# isolated_USB.net
KiCad netlist of a schematic drawn in Altium Designer
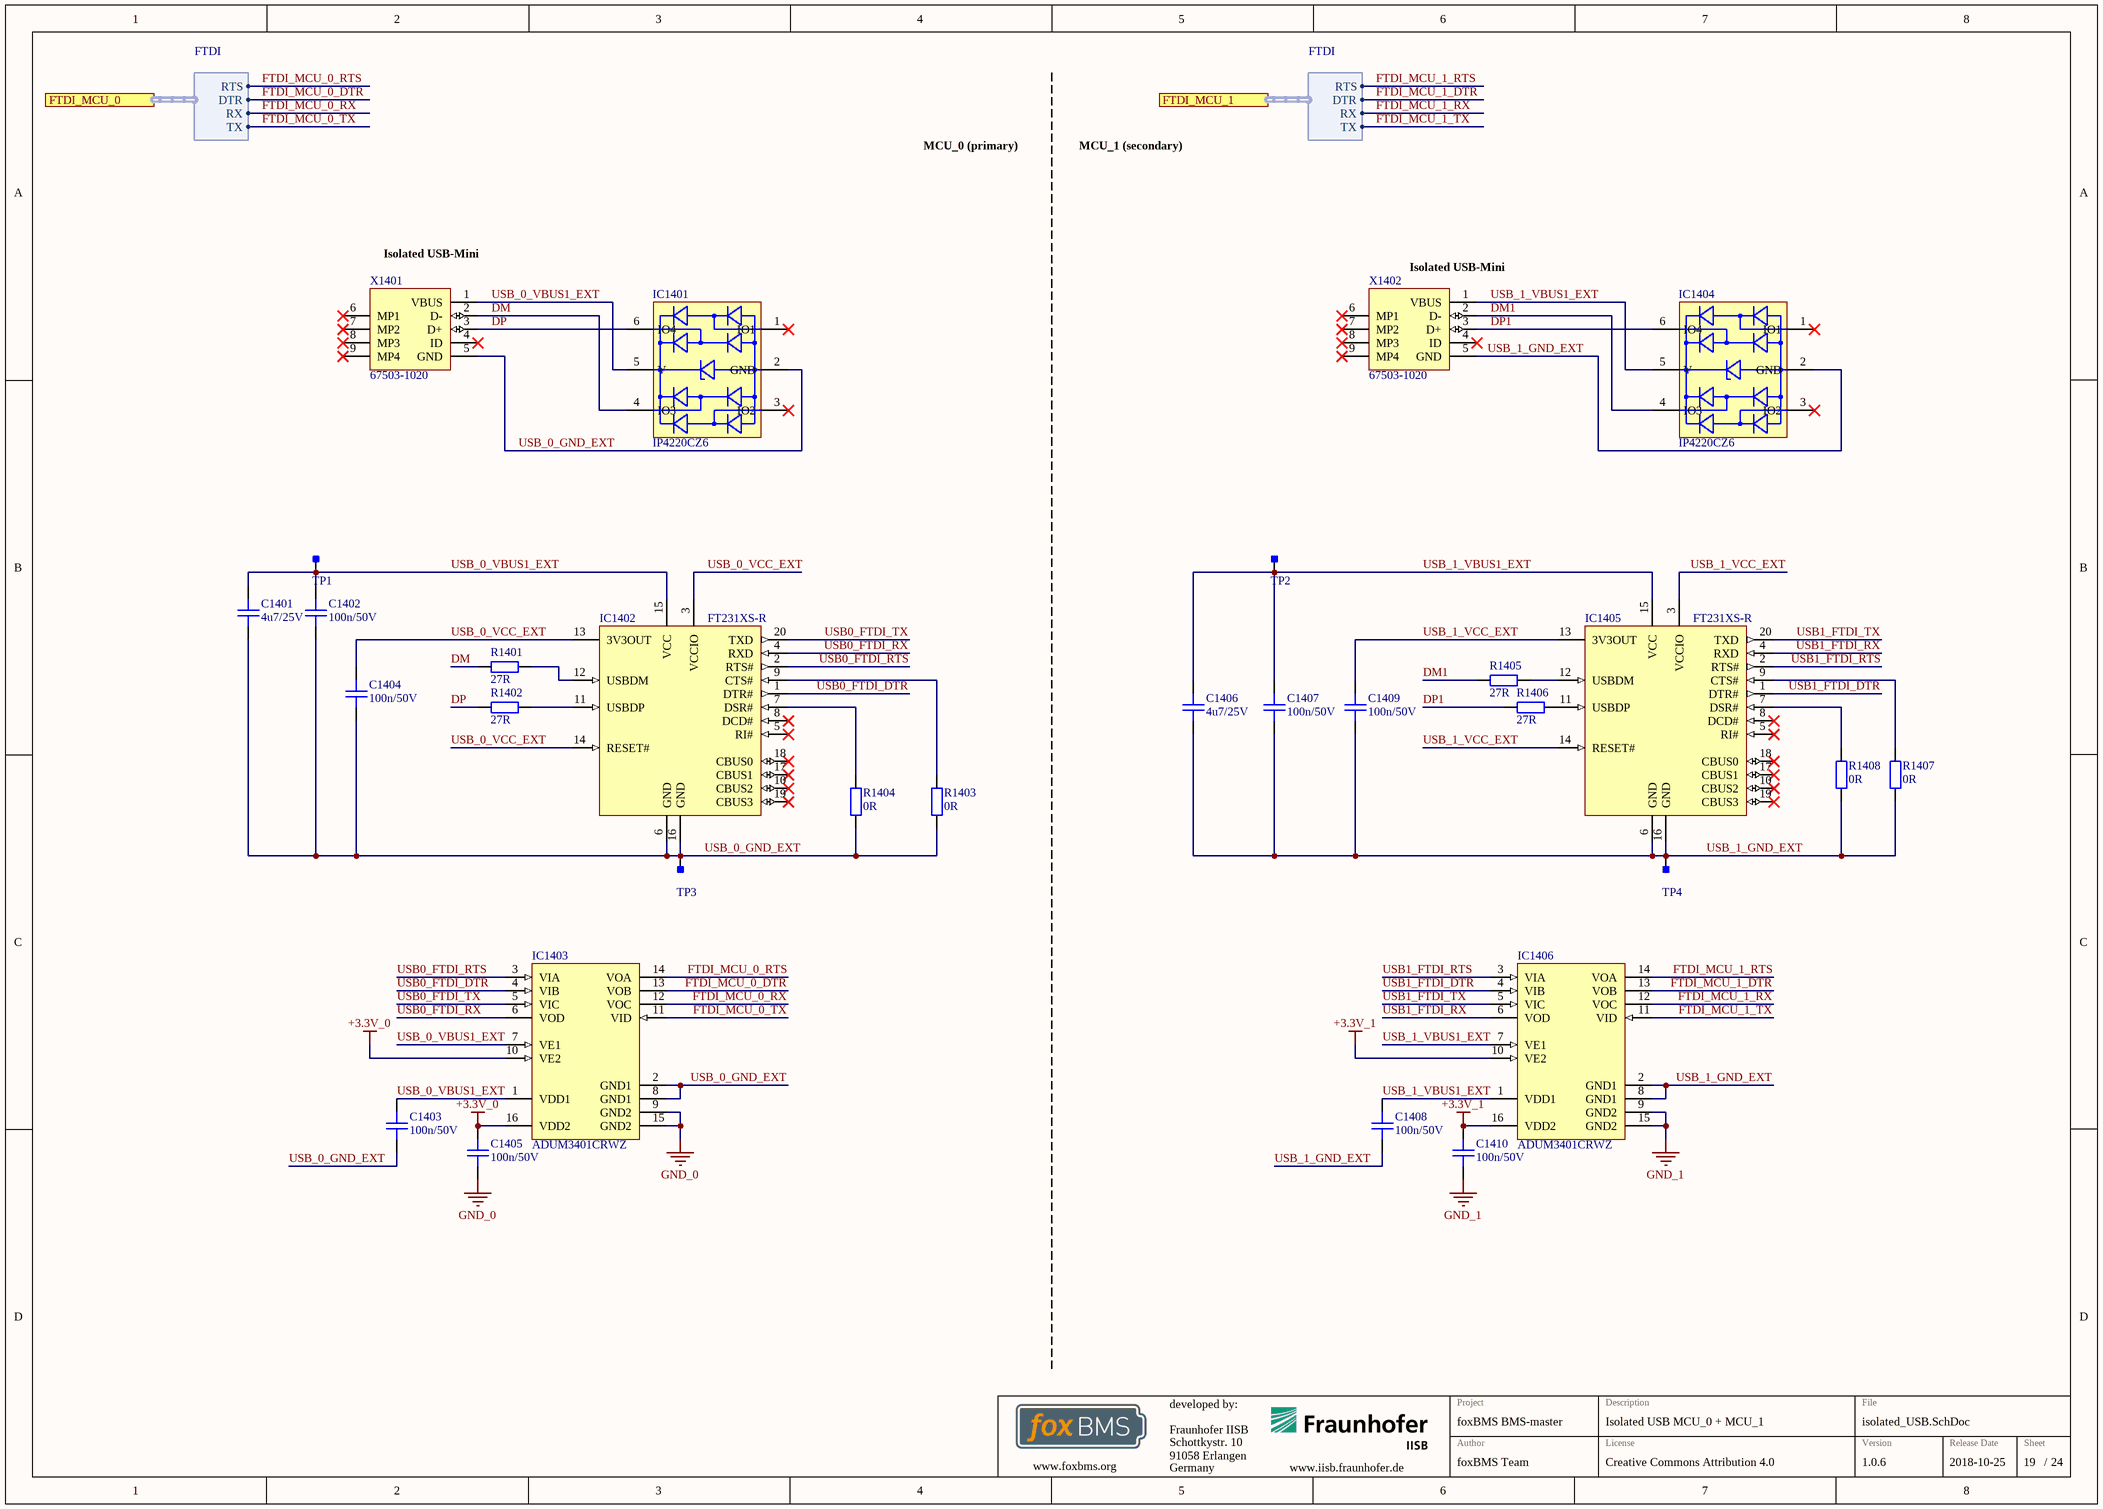
[diagram p0: isolated_USB.SchDoc]

(export (version "E")
  (design (tool "Eeschema 10.0.6"))
  (components
    (comp (ref "C1401")
      (value "4u7/25V")
      (footprint "CAPC1608X08N")
      (description "MLCC")
      (fields (field (name "PART NUMBER") "gen_C_ceramic_4u7_25V_X5R_0603"))
      (libsource (lib "OE750") (part "C"))
    )
    (comp (ref "C1402")
      (value "100n/50V")
      (footprint "CAPC1608X08N")
      (description "MLCC")
      (fields (field (name "PART NUMBER") "gen_C_ceramic_100n_50V_X7R_0603"))
      (libsource (lib "OE750") (part "C"))
    )
    (comp (ref "C1403")
      (value "100n/50V")
      (footprint "CAPC1608X08N")
      (description "MLCC")
      (fields (field (name "PART NUMBER") "gen_C_ceramic_100n_50V_X7R_0603"))
      (libsource (lib "OE750") (part "C"))
    )
    (comp (ref "C1404")
      (value "100n/50V")
      (footprint "CAPC1608X08N")
      (description "MLCC")
      (fields (field (name "PART NUMBER") "gen_C_ceramic_100n_50V_X7R_0603"))
      (libsource (lib "OE750") (part "C"))
    )
    (comp (ref "C1405")
      (value "100n/50V")
      (footprint "CAPC1608X08N")
      (description "MLCC")
      (fields (field (name "PART NUMBER") "gen_C_ceramic_100n_50V_X7R_0603"))
      (libsource (lib "OE750") (part "C"))
    )
    (comp (ref "C1406")
      (value "4u7/25V")
      (footprint "CAPC1608X08N")
      (description "MLCC")
      (fields (field (name "PART NUMBER") "gen_C_ceramic_4u7_25V_X5R_0603"))
      (libsource (lib "OE750") (part "C"))
    )
    (comp (ref "C1407")
      (value "100n/50V")
      (footprint "CAPC1608X08N")
      (description "MLCC")
      (fields (field (name "PART NUMBER") "gen_C_ceramic_100n_50V_X7R_0603"))
      (libsource (lib "OE750") (part "C"))
    )
    (comp (ref "C1408")
      (value "100n/50V")
      (footprint "CAPC1608X08N")
      (description "MLCC")
      (fields (field (name "PART NUMBER") "gen_C_ceramic_100n_50V_X7R_0603"))
      (libsource (lib "OE750") (part "C"))
    )
    (comp (ref "C1409")
      (value "100n/50V")
      (footprint "CAPC1608X08N")
      (description "MLCC")
      (fields (field (name "PART NUMBER") "gen_C_ceramic_100n_50V_X7R_0603"))
      (libsource (lib "OE750") (part "C"))
    )
    (comp (ref "C1410")
      (value "100n/50V")
      (footprint "CAPC1608X08N")
      (description "MLCC")
      (fields (field (name "PART NUMBER") "gen_C_ceramic_100n_50V_X7R_0603"))
      (libsource (lib "OE750") (part "C"))
    )
    (comp (ref "IC1401")
      (value "IP4220CZ6")
      (footprint "TSOP95P280X110-6N")
      (description "Usb ESD protection diodes")
      (fields
        (field (name "PART NUMBER") "nxp_IP4220CZ6,125\r\nIP4220CZ6,125")
        (field (name "MANUFACTURER") "Nexperia")
      )
      (libsource (lib "OE750") (part "IP4220CZ6"))
    )
    (comp (ref "IC1402")
      (value "FT231XS-R")
      (footprint "SSOP-20_L")
      (fields (field (name "MANUFACTURER") "FTDI"))
      (libsource (lib "Altium Content Vault") (part "COM-USB-FT231XS-IL20"))
    )
    (comp (ref "IC1403")
      (value "ADUM3401CRWZ")
      (footprint "ADI-RW-16_N")
      (fields (field (name "MANUFACTURER") "Analog Devices"))
      (libsource (lib "Altium Content Vault") (part "ADI-ADUMX4X1-16"))
    )
    (comp (ref "IC1404")
      (value "IP4220CZ6")
      (footprint "TSOP95P280X110-6N")
      (description "Usb ESD protection diodes")
      (fields
        (field (name "PART NUMBER") "nxp_IP4220CZ6,125\r\nIP4220CZ6,125")
        (field (name "MANUFACTURER") "Nexperia")
      )
      (libsource (lib "OE750") (part "IP4220CZ6"))
    )
    (comp (ref "IC1405")
      (value "FT231XS-R")
      (footprint "SSOP-20_L")
      (fields (field (name "MANUFACTURER") "FTDI"))
      (libsource (lib "Altium Content Vault") (part "COM-USB-FT231XS-IL20"))
    )
    (comp (ref "IC1406")
      (value "ADUM3401CRWZ")
      (footprint "ADI-RW-16_N")
      (fields (field (name "MANUFACTURER") "Analog Devices"))
      (libsource (lib "Altium Content Vault") (part "ADI-ADUMX4X1-16"))
    )
    (comp (ref "R1401")
      (value "27R")
      (footprint "RESC1608X05N")
      (description "SMD Resistor 27R 0603")
      (fields (field (name "PART NUMBER") "gen_R_27R_0603") (field (name "TOLERANCE") "1%"))
      (libsource (lib "OE750") (part "R"))
    )
    (comp (ref "R1402")
      (value "27R")
      (footprint "RESC1608X05N")
      (description "SMD Resistor 27R 0603")
      (fields (field (name "PART NUMBER") "gen_R_27R_0603") (field (name "TOLERANCE") "1%"))
      (libsource (lib "OE750") (part "R"))
    )
    (comp (ref "R1403")
      (value "0R")
      (footprint "RESC1608X05N")
      (description "SMD Resistor 0R 0603")
      (fields (field (name "PART NUMBER") "gen_R_0R_0603") (field (name "POWER") "0.1W"))
      (libsource (lib "OE750") (part "R"))
    )
    (comp (ref "R1404")
      (value "0R")
      (footprint "RESC1608X05N")
      (description "SMD Resistor 0R 0603")
      (fields (field (name "PART NUMBER") "gen_R_0R_0603") (field (name "POWER") "0.1W"))
      (libsource (lib "OE750") (part "R"))
    )
    (comp (ref "R1405")
      (value "27R")
      (footprint "RESC1608X05N")
      (description "SMD Resistor 27R 0603")
      (fields (field (name "PART NUMBER") "gen_R_27R_0603") (field (name "TOLERANCE") "1%"))
      (libsource (lib "OE750") (part "R"))
    )
    (comp (ref "R1406")
      (value "27R")
      (footprint "RESC1608X05N")
      (description "SMD Resistor 27R 0603")
      (fields (field (name "PART NUMBER") "gen_R_27R_0603") (field (name "TOLERANCE") "1%"))
      (libsource (lib "OE750") (part "R"))
    )
    (comp (ref "R1407")
      (value "0R")
      (footprint "RESC1608X05N")
      (description "SMD Resistor 0R 0603")
      (fields (field (name "PART NUMBER") "gen_R_0R_0603") (field (name "POWER") "0.1W"))
      (libsource (lib "OE750") (part "R"))
    )
    (comp (ref "R1408")
      (value "0R")
      (footprint "RESC1608X05N")
      (description "SMD Resistor 0R 0603")
      (fields (field (name "PART NUMBER") "gen_R_0R_0603") (field (name "POWER") "0.1W"))
      (libsource (lib "OE750") (part "R"))
    )
    (comp (ref "TP1")
      (value "Testpoint_Square")
      (footprint "Testpoint_S1")
      (description "Testpoint, square")
      (libsource (lib "OE750") (part "Testpoint_Square"))
    )
    (comp (ref "TP2")
      (value "Testpoint_Square")
      (footprint "Testpoint_S1")
      (description "Testpoint, square")
      (libsource (lib "OE750") (part "Testpoint_Square"))
    )
    (comp (ref "TP3")
      (value "Testpoint_Square")
      (footprint "Testpoint_S1")
      (description "Testpoint, square")
      (libsource (lib "OE750") (part "Testpoint_Square"))
    )
    (comp (ref "TP4")
      (value "Testpoint_Square")
      (footprint "Testpoint_S1")
      (description "Testpoint, square")
      (libsource (lib "OE750") (part "Testpoint_Square"))
    )
    (comp (ref "X1401")
      (value "67503-1020")
      (footprint "MOLX-67503-1020_V")
      (description "USB, MINI, SMD, RA KME04-USBMU03A01")
      (fields (field (name "MANUFACTURER") "Molex"))
      (libsource (lib "Altium Content Vault") (part "MOLX-67503-1020"))
    )
    (comp (ref "X1402")
      (value "67503-1020")
      (footprint "MOLX-67503-1020_V")
      (description "USB, MINI, SMD, RA KME04-USBMU03A01")
      (fields (field (name "MANUFACTURER") "Molex"))
      (libsource (lib "Altium Content Vault") (part "MOLX-67503-1020"))
    )
  )
  (nets
    (net (code "2") (name "+3.3V_0") (class "Default")
      (node (ref "C1405") (pin "1") (pinfunction "1_1") (pintype "passive"))
      (node (ref "IC1403") (pin "10") (pinfunction "VE2_10") (pintype "input"))
      (node (ref "IC1403") (pin "16") (pinfunction "VDD2_16") (pintype "power_in"))
    )
    (net (code "3") (name "+3.3V_1") (class "Default")
      (node (ref "C1410") (pin "1") (pinfunction "1_1") (pintype "passive"))
      (node (ref "IC1406") (pin "10") (pinfunction "VE2_10") (pintype "input"))
      (node (ref "IC1406") (pin "16") (pinfunction "VDD2_16") (pintype "power_in"))
    )
    (net (code "4") (name "/DM") (class "Default")
      (node (ref "IC1401") (pin "4") (pinfunction "IO3_4") (pintype "passive"))
      (node (ref "R1401") (pin "2") (pinfunction "2_2") (pintype "passive"))
      (node (ref "X1401") (pin "2") (pinfunction "D-_2") (pintype "bidirectional"))
    )
    (net (code "5") (name "/DM1") (class "Default")
      (node (ref "IC1404") (pin "4") (pinfunction "IO3_4") (pintype "passive"))
      (node (ref "R1405") (pin "2") (pinfunction "2_2") (pintype "passive"))
      (node (ref "X1402") (pin "2") (pinfunction "D-_2") (pintype "bidirectional"))
    )
    (net (code "6") (name "/DP") (class "Default")
      (node (ref "IC1401") (pin "6") (pinfunction "IO4_6") (pintype "passive"))
      (node (ref "R1402") (pin "2") (pinfunction "2_2") (pintype "passive"))
      (node (ref "X1401") (pin "3") (pinfunction "D+_3") (pintype "bidirectional"))
    )
    (net (code "7") (name "/DP1") (class "Default")
      (node (ref "IC1404") (pin "6") (pinfunction "IO4_6") (pintype "passive"))
      (node (ref "R1406") (pin "2") (pinfunction "2_2") (pintype "passive"))
      (node (ref "X1402") (pin "3") (pinfunction "D+_3") (pintype "bidirectional"))
    )
    (net (code "8") (name "/FTDI_MCU_0_DTR") (class "Default")
      (node (ref "IC1403") (pin "13") (pinfunction "VOB_13") (pintype "tri_state"))
    )
    (net (code "9") (name "/FTDI_MCU_0_RTS") (class "Default")
      (node (ref "IC1403") (pin "14") (pinfunction "VOA_14") (pintype "tri_state"))
    )
    (net (code "10") (name "/FTDI_MCU_0_RX") (class "Default")
      (node (ref "IC1403") (pin "12") (pinfunction "VOC_12") (pintype "tri_state"))
    )
    (net (code "11") (name "/FTDI_MCU_0_TX") (class "Default")
      (node (ref "IC1403") (pin "11") (pinfunction "VID_11") (pintype "input"))
    )
    (net (code "12") (name "/FTDI_MCU_1_DTR") (class "Default")
      (node (ref "IC1406") (pin "13") (pinfunction "VOB_13") (pintype "tri_state"))
    )
    (net (code "13") (name "/FTDI_MCU_1_RTS") (class "Default")
      (node (ref "IC1406") (pin "14") (pinfunction "VOA_14") (pintype "tri_state"))
    )
    (net (code "14") (name "/FTDI_MCU_1_RX") (class "Default")
      (node (ref "IC1406") (pin "12") (pinfunction "VOC_12") (pintype "tri_state"))
    )
    (net (code "15") (name "/FTDI_MCU_1_TX") (class "Default")
      (node (ref "IC1406") (pin "11") (pinfunction "VID_11") (pintype "input"))
    )
    (net (code "16") (name "/USB0_FTDI_DTR") (class "Default")
      (node (ref "IC1402") (pin "1") (pinfunction "DTR#_1") (pintype "output"))
      (node (ref "IC1403") (pin "4") (pinfunction "VIB_4") (pintype "input"))
    )
    (net (code "17") (name "/USB0_FTDI_RTS") (class "Default")
      (node (ref "IC1402") (pin "2") (pinfunction "RTS#_2") (pintype "output"))
      (node (ref "IC1403") (pin "3") (pinfunction "VIA_3") (pintype "input"))
    )
    (net (code "18") (name "/USB0_FTDI_RX") (class "Default")
      (node (ref "IC1402") (pin "4") (pinfunction "RXD_4") (pintype "input"))
      (node (ref "IC1403") (pin "6") (pinfunction "VOD_6") (pintype "tri_state"))
    )
    (net (code "19") (name "/USB0_FTDI_TX") (class "Default")
      (node (ref "IC1402") (pin "20") (pinfunction "TXD_20") (pintype "output"))
      (node (ref "IC1403") (pin "5") (pinfunction "VIC_5") (pintype "input"))
    )
    (net (code "20") (name "/USB1_FTDI_DTR") (class "Default")
      (node (ref "IC1405") (pin "1") (pinfunction "DTR#_1") (pintype "output"))
      (node (ref "IC1406") (pin "4") (pinfunction "VIB_4") (pintype "input"))
    )
    (net (code "21") (name "/USB1_FTDI_RTS") (class "Default")
      (node (ref "IC1405") (pin "2") (pinfunction "RTS#_2") (pintype "output"))
      (node (ref "IC1406") (pin "3") (pinfunction "VIA_3") (pintype "input"))
    )
    (net (code "22") (name "/USB1_FTDI_RX") (class "Default")
      (node (ref "IC1405") (pin "4") (pinfunction "RXD_4") (pintype "input"))
      (node (ref "IC1406") (pin "6") (pinfunction "VOD_6") (pintype "tri_state"))
    )
    (net (code "23") (name "/USB1_FTDI_TX") (class "Default")
      (node (ref "IC1405") (pin "20") (pinfunction "TXD_20") (pintype "output"))
      (node (ref "IC1406") (pin "5") (pinfunction "VIC_5") (pintype "input"))
    )
    (net (code "24") (name "/USB_0_GND_EXT") (class "Default")
      (node (ref "C1401") (pin "2") (pinfunction "2_2") (pintype "passive"))
      (node (ref "C1402") (pin "2") (pinfunction "2_2") (pintype "passive"))
      (node (ref "C1403") (pin "2") (pinfunction "2_2") (pintype "passive"))
      (node (ref "C1404") (pin "2") (pinfunction "2_2") (pintype "passive"))
      (node (ref "IC1401") (pin "2") (pinfunction "GND_2") (pintype "passive"))
      (node (ref "IC1402") (pin "16") (pinfunction "GND_16") (pintype "power_in"))
      (node (ref "IC1402") (pin "6") (pinfunction "GND_6") (pintype "power_in"))
      (node (ref "IC1403") (pin "2") (pinfunction "GND1_2") (pintype "power_in"))
      (node (ref "IC1403") (pin "8") (pinfunction "GND1_8") (pintype "power_in"))
      (node (ref "R1403") (pin "2") (pinfunction "2_2") (pintype "passive"))
      (node (ref "R1404") (pin "2") (pinfunction "2_2") (pintype "passive"))
      (node (ref "TP3") (pin "1") (pinfunction "1_1") (pintype "passive"))
      (node (ref "X1401") (pin "5") (pinfunction "GND_5") (pintype "power_in"))
    )
    (net (code "25") (name "/USB_0_VBUS1_EXT") (class "Default")
      (node (ref "C1401") (pin "1") (pinfunction "1_1") (pintype "passive"))
      (node (ref "C1402") (pin "1") (pinfunction "1_1") (pintype "passive"))
      (node (ref "C1403") (pin "1") (pinfunction "1_1") (pintype "passive"))
      (node (ref "IC1401") (pin "5") (pinfunction "V_5") (pintype "passive"))
      (node (ref "IC1402") (pin "15") (pinfunction "VCC_15") (pintype "power_in"))
      (node (ref "IC1403") (pin "1") (pinfunction "VDD1_1") (pintype "power_in"))
      (node (ref "IC1403") (pin "7") (pinfunction "VE1_7") (pintype "input"))
      (node (ref "TP1") (pin "1") (pinfunction "1_1") (pintype "passive"))
      (node (ref "X1401") (pin "1") (pinfunction "VBUS_1") (pintype "power_in"))
    )
    (net (code "26") (name "/USB_0_VCC_EXT") (class "Default")
      (node (ref "C1404") (pin "1") (pinfunction "1_1") (pintype "passive"))
      (node (ref "IC1402") (pin "13") (pinfunction "3V3OUT_13") (pintype "power_in"))
      (node (ref "IC1402") (pin "14") (pinfunction "RESET#_14") (pintype "input"))
      (node (ref "IC1402") (pin "3") (pinfunction "VCCIO_3") (pintype "power_in"))
    )
    (net (code "27") (name "/USB_1_GND_EXT") (class "Default")
      (node (ref "C1406") (pin "2") (pinfunction "2_2") (pintype "passive"))
      (node (ref "C1407") (pin "2") (pinfunction "2_2") (pintype "passive"))
      (node (ref "C1408") (pin "2") (pinfunction "2_2") (pintype "passive"))
      (node (ref "C1409") (pin "2") (pinfunction "2_2") (pintype "passive"))
      (node (ref "IC1404") (pin "2") (pinfunction "GND_2") (pintype "passive"))
      (node (ref "IC1405") (pin "16") (pinfunction "GND_16") (pintype "power_in"))
      (node (ref "IC1405") (pin "6") (pinfunction "GND_6") (pintype "power_in"))
      (node (ref "IC1406") (pin "2") (pinfunction "GND1_2") (pintype "power_in"))
      (node (ref "IC1406") (pin "8") (pinfunction "GND1_8") (pintype "power_in"))
      (node (ref "R1407") (pin "2") (pinfunction "2_2") (pintype "passive"))
      (node (ref "R1408") (pin "2") (pinfunction "2_2") (pintype "passive"))
      (node (ref "TP4") (pin "1") (pinfunction "1_1") (pintype "passive"))
      (node (ref "X1402") (pin "5") (pinfunction "GND_5") (pintype "power_in"))
    )
    (net (code "28") (name "/USB_1_VBUS1_EXT") (class "Default")
      (node (ref "C1406") (pin "1") (pinfunction "1_1") (pintype "passive"))
      (node (ref "C1407") (pin "1") (pinfunction "1_1") (pintype "passive"))
      (node (ref "C1408") (pin "1") (pinfunction "1_1") (pintype "passive"))
      (node (ref "IC1404") (pin "5") (pinfunction "V_5") (pintype "passive"))
      (node (ref "IC1405") (pin "15") (pinfunction "VCC_15") (pintype "power_in"))
      (node (ref "IC1406") (pin "1") (pinfunction "VDD1_1") (pintype "power_in"))
      (node (ref "IC1406") (pin "7") (pinfunction "VE1_7") (pintype "input"))
      (node (ref "TP2") (pin "1") (pinfunction "1_1") (pintype "passive"))
      (node (ref "X1402") (pin "1") (pinfunction "VBUS_1") (pintype "power_in"))
    )
    (net (code "29") (name "/USB_1_VCC_EXT") (class "Default")
      (node (ref "C1409") (pin "1") (pinfunction "1_1") (pintype "passive"))
      (node (ref "IC1405") (pin "13") (pinfunction "3V3OUT_13") (pintype "power_in"))
      (node (ref "IC1405") (pin "14") (pinfunction "RESET#_14") (pintype "input"))
      (node (ref "IC1405") (pin "3") (pinfunction "VCCIO_3") (pintype "power_in"))
    )
    (net (code "31") (name "GND_0") (class "Default")
      (node (ref "C1405") (pin "2") (pinfunction "2_2") (pintype "passive"))
      (node (ref "IC1403") (pin "15") (pinfunction "GND2_15") (pintype "power_in"))
      (node (ref "IC1403") (pin "9") (pinfunction "GND2_9") (pintype "power_in"))
    )
    (net (code "32") (name "GND_1") (class "Default")
      (node (ref "C1410") (pin "2") (pinfunction "2_2") (pintype "passive"))
      (node (ref "IC1406") (pin "15") (pinfunction "GND2_15") (pintype "power_in"))
      (node (ref "IC1406") (pin "9") (pinfunction "GND2_9") (pintype "power_in"))
    )
    (net (code "33") (name "Net-(IC1402-CTS#)") (class "Default")
      (node (ref "IC1402") (pin "9") (pinfunction "CTS#_9") (pintype "input"))
      (node (ref "R1403") (pin "1") (pinfunction "1_1") (pintype "passive"))
    )
    (net (code "34") (name "Net-(IC1402-DSR#)") (class "Default")
      (node (ref "IC1402") (pin "7") (pinfunction "DSR#_7") (pintype "input"))
      (node (ref "R1404") (pin "1") (pinfunction "1_1") (pintype "passive"))
    )
    (net (code "35") (name "Net-(IC1402-USBDM)") (class "Default")
      (node (ref "IC1402") (pin "12") (pinfunction "USBDM_12") (pintype "input"))
      (node (ref "R1401") (pin "1") (pinfunction "1_1") (pintype "passive"))
    )
    (net (code "36") (name "Net-(IC1402-USBDP)") (class "Default")
      (node (ref "IC1402") (pin "11") (pinfunction "USBDP_11") (pintype "input"))
      (node (ref "R1402") (pin "1") (pinfunction "1_1") (pintype "passive"))
    )
    (net (code "37") (name "Net-(IC1405-CTS#)") (class "Default")
      (node (ref "IC1405") (pin "9") (pinfunction "CTS#_9") (pintype "input"))
      (node (ref "R1407") (pin "1") (pinfunction "1_1") (pintype "passive"))
    )
    (net (code "38") (name "Net-(IC1405-DSR#)") (class "Default")
      (node (ref "IC1405") (pin "7") (pinfunction "DSR#_7") (pintype "input"))
      (node (ref "R1408") (pin "1") (pinfunction "1_1") (pintype "passive"))
    )
    (net (code "39") (name "Net-(IC1405-USBDM)") (class "Default")
      (node (ref "IC1405") (pin "12") (pinfunction "USBDM_12") (pintype "input"))
      (node (ref "R1405") (pin "1") (pinfunction "1_1") (pintype "passive"))
    )
    (net (code "40") (name "Net-(IC1405-USBDP)") (class "Default")
      (node (ref "IC1405") (pin "11") (pinfunction "USBDP_11") (pintype "input"))
      (node (ref "R1406") (pin "1") (pinfunction "1_1") (pintype "passive"))
    )
    (net (code "41") (name "unconnected-(IC1401-IO1-Pad1)") (class "Default")
      (node (ref "IC1401") (pin "1") (pinfunction "IO1_1") (pintype "passive+no_connect"))
    )
    (net (code "42") (name "unconnected-(IC1401-IO2-Pad3)") (class "Default")
      (node (ref "IC1401") (pin "3") (pinfunction "IO2_3") (pintype "passive+no_connect"))
    )
    (net (code "43") (name "unconnected-(IC1402-CBUS0-Pad18)") (class "Default")
      (node (ref "IC1402") (pin "18") (pinfunction "CBUS0_18") (pintype "bidirectional+no_connect"))
    )
    (net (code "44") (name "unconnected-(IC1402-CBUS1-Pad17)") (class "Default")
      (node (ref "IC1402") (pin "17") (pinfunction "CBUS1_17") (pintype "bidirectional+no_connect"))
    )
    (net (code "45") (name "unconnected-(IC1402-CBUS2-Pad10)") (class "Default")
      (node (ref "IC1402") (pin "10") (pinfunction "CBUS2_10") (pintype "bidirectional+no_connect"))
    )
    (net (code "46") (name "unconnected-(IC1402-CBUS3-Pad19)") (class "Default")
      (node (ref "IC1402") (pin "19") (pinfunction "CBUS3_19") (pintype "bidirectional+no_connect"))
    )
    (net (code "47") (name "unconnected-(IC1402-DCD#-Pad8)") (class "Default")
      (node (ref "IC1402") (pin "8") (pinfunction "DCD#_8") (pintype "input+no_connect"))
    )
    (net (code "48") (name "unconnected-(IC1402-RI#-Pad5)") (class "Default")
      (node (ref "IC1402") (pin "5") (pinfunction "RI#_5") (pintype "input+no_connect"))
    )
    (net (code "49") (name "unconnected-(IC1404-IO1-Pad1)") (class "Default")
      (node (ref "IC1404") (pin "1") (pinfunction "IO1_1") (pintype "passive+no_connect"))
    )
    (net (code "50") (name "unconnected-(IC1404-IO2-Pad3)") (class "Default")
      (node (ref "IC1404") (pin "3") (pinfunction "IO2_3") (pintype "passive+no_connect"))
    )
    (net (code "51") (name "unconnected-(IC1405-CBUS0-Pad18)") (class "Default")
      (node (ref "IC1405") (pin "18") (pinfunction "CBUS0_18") (pintype "bidirectional+no_connect"))
    )
    (net (code "52") (name "unconnected-(IC1405-CBUS1-Pad17)") (class "Default")
      (node (ref "IC1405") (pin "17") (pinfunction "CBUS1_17") (pintype "bidirectional+no_connect"))
    )
    (net (code "53") (name "unconnected-(IC1405-CBUS2-Pad10)") (class "Default")
      (node (ref "IC1405") (pin "10") (pinfunction "CBUS2_10") (pintype "bidirectional+no_connect"))
    )
    (net (code "54") (name "unconnected-(IC1405-CBUS3-Pad19)") (class "Default")
      (node (ref "IC1405") (pin "19") (pinfunction "CBUS3_19") (pintype "bidirectional+no_connect"))
    )
    (net (code "55") (name "unconnected-(IC1405-DCD#-Pad8)") (class "Default")
      (node (ref "IC1405") (pin "8") (pinfunction "DCD#_8") (pintype "input+no_connect"))
    )
    (net (code "56") (name "unconnected-(IC1405-RI#-Pad5)") (class "Default")
      (node (ref "IC1405") (pin "5") (pinfunction "RI#_5") (pintype "input+no_connect"))
    )
    (net (code "57") (name "unconnected-(X1401-ID-Pad4)") (class "Default")
      (node (ref "X1401") (pin "4") (pinfunction "ID_4") (pintype "passive+no_connect"))
    )
    (net (code "58") (name "unconnected-(X1401-MP1-Pad6)") (class "Default")
      (node (ref "X1401") (pin "6") (pinfunction "MP1_6") (pintype "passive+no_connect"))
    )
    (net (code "59") (name "unconnected-(X1401-MP2-Pad7)") (class "Default")
      (node (ref "X1401") (pin "7") (pinfunction "MP2_7") (pintype "passive+no_connect"))
    )
    (net (code "60") (name "unconnected-(X1401-MP3-Pad8)") (class "Default")
      (node (ref "X1401") (pin "8") (pinfunction "MP3_8") (pintype "passive+no_connect"))
    )
    (net (code "61") (name "unconnected-(X1401-MP4-Pad9)") (class "Default")
      (node (ref "X1401") (pin "9") (pinfunction "MP4_9") (pintype "passive+no_connect"))
    )
    (net (code "62") (name "unconnected-(X1402-ID-Pad4)") (class "Default")
      (node (ref "X1402") (pin "4") (pinfunction "ID_4") (pintype "passive+no_connect"))
    )
    (net (code "63") (name "unconnected-(X1402-MP1-Pad6)") (class "Default")
      (node (ref "X1402") (pin "6") (pinfunction "MP1_6") (pintype "passive+no_connect"))
    )
    (net (code "64") (name "unconnected-(X1402-MP2-Pad7)") (class "Default")
      (node (ref "X1402") (pin "7") (pinfunction "MP2_7") (pintype "passive+no_connect"))
    )
    (net (code "65") (name "unconnected-(X1402-MP3-Pad8)") (class "Default")
      (node (ref "X1402") (pin "8") (pinfunction "MP3_8") (pintype "passive+no_connect"))
    )
    (net (code "66") (name "unconnected-(X1402-MP4-Pad9)") (class "Default")
      (node (ref "X1402") (pin "9") (pinfunction "MP4_9") (pintype "passive+no_connect"))
    )
  )
)
